# stlink_mount.net
KiCad netlist of a schematic drawn in EAGLE
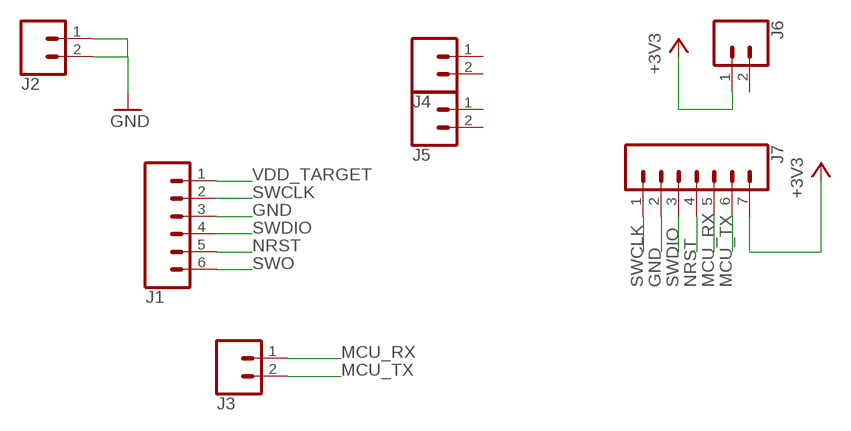
[diagram p0: schematic, sheet 1]

(export (version "E")
  (design (tool "Eeschema 10.0.6"))
  (components
    (comp (ref "J1")
      (value "CONN_06SILK_FEMALE_PTH")
      (footprint "eagle-import:1X06")
      (libsource (lib "eagle-import") (part "CONN_06SILK_FEMALE_PTH"))
    )
    (comp (ref "J2")
      (value "CONN_02")
      (footprint "eagle-import:1X02")
      (libsource (lib "eagle-import") (part "CONN_02"))
    )
    (comp (ref "J3")
      (value "CONN_02")
      (footprint "eagle-import:1X02")
      (libsource (lib "eagle-import") (part "CONN_02"))
    )
    (comp (ref "J4")
      (value "CONN_02")
      (footprint "eagle-import:1X02")
      (libsource (lib "eagle-import") (part "CONN_02"))
    )
    (comp (ref "J5")
      (value "CONN_02")
      (footprint "eagle-import:1X02")
      (libsource (lib "eagle-import") (part "CONN_02"))
    )
    (comp (ref "J6")
      (value "CONN_02")
      (footprint "eagle-import:1X02")
      (libsource (lib "eagle-import") (part "CONN_02"))
    )
    (comp (ref "J7")
      (value "CONN_07")
      (footprint "eagle-import:1X07")
      (libsource (lib "eagle-import") (part "CONN_07"))
    )
  )
  (nets
    (net (code "1") (name "+3V3") (class "Default")
      (node (ref "J6") (pin "1") (pinfunction "1_1") (pintype "passive"))
      (node (ref "J7") (pin "7") (pinfunction "7_7") (pintype "passive"))
    )
    (net (code "2") (name "/MCU_RX") (class "Default")
      (node (ref "J3") (pin "1") (pinfunction "1_1") (pintype "passive"))
      (node (ref "J7") (pin "5") (pinfunction "5_5") (pintype "passive"))
    )
    (net (code "3") (name "/MCU_TX") (class "Default")
      (node (ref "J3") (pin "2") (pinfunction "2_2") (pintype "passive"))
      (node (ref "J7") (pin "6") (pinfunction "6_6") (pintype "passive"))
    )
    (net (code "4") (name "/NRST") (class "Default")
      (node (ref "J1") (pin "5") (pinfunction "5_5") (pintype "passive"))
      (node (ref "J7") (pin "4") (pinfunction "4_4") (pintype "passive"))
    )
    (net (code "5") (name "/SWCLK") (class "Default")
      (node (ref "J1") (pin "2") (pinfunction "2_2") (pintype "passive"))
      (node (ref "J7") (pin "1") (pinfunction "1_1") (pintype "passive"))
    )
    (net (code "6") (name "/SWDIO") (class "Default")
      (node (ref "J1") (pin "4") (pinfunction "4_4") (pintype "passive"))
      (node (ref "J7") (pin "3") (pinfunction "3_3") (pintype "passive"))
    )
    (net (code "7") (name "/SWO") (class "Default")
      (node (ref "J1") (pin "6") (pinfunction "6_6") (pintype "passive"))
    )
    (net (code "8") (name "/VDD_TARGET") (class "Default")
      (node (ref "J1") (pin "1") (pinfunction "1_1") (pintype "passive"))
    )
    (net (code "9") (name "GND") (class "Default")
      (node (ref "J1") (pin "3") (pinfunction "3_3") (pintype "passive"))
      (node (ref "J2") (pin "1") (pinfunction "1_1") (pintype "passive"))
      (node (ref "J2") (pin "2") (pinfunction "2_2") (pintype "passive"))
      (node (ref "J7") (pin "2") (pinfunction "2_2") (pintype "passive"))
    )
    (net (code "10") (name "unconnected-(J4-Pad1)") (class "Default")
      (node (ref "J4") (pin "1") (pinfunction "1_1") (pintype "passive"))
    )
    (net (code "11") (name "unconnected-(J4-Pad2)") (class "Default")
      (node (ref "J4") (pin "2") (pinfunction "2_2") (pintype "passive"))
    )
    (net (code "12") (name "unconnected-(J5-Pad1)") (class "Default")
      (node (ref "J5") (pin "1") (pinfunction "1_1") (pintype "passive"))
    )
    (net (code "13") (name "unconnected-(J5-Pad2)") (class "Default")
      (node (ref "J5") (pin "2") (pinfunction "2_2") (pintype "passive"))
    )
    (net (code "14") (name "unconnected-(J6-Pad2)") (class "Default")
      (node (ref "J6") (pin "2") (pinfunction "2_2") (pintype "passive"))
    )
  )
)
